# M850X.net
KiCad netlist of a schematic drawn in EAGLE
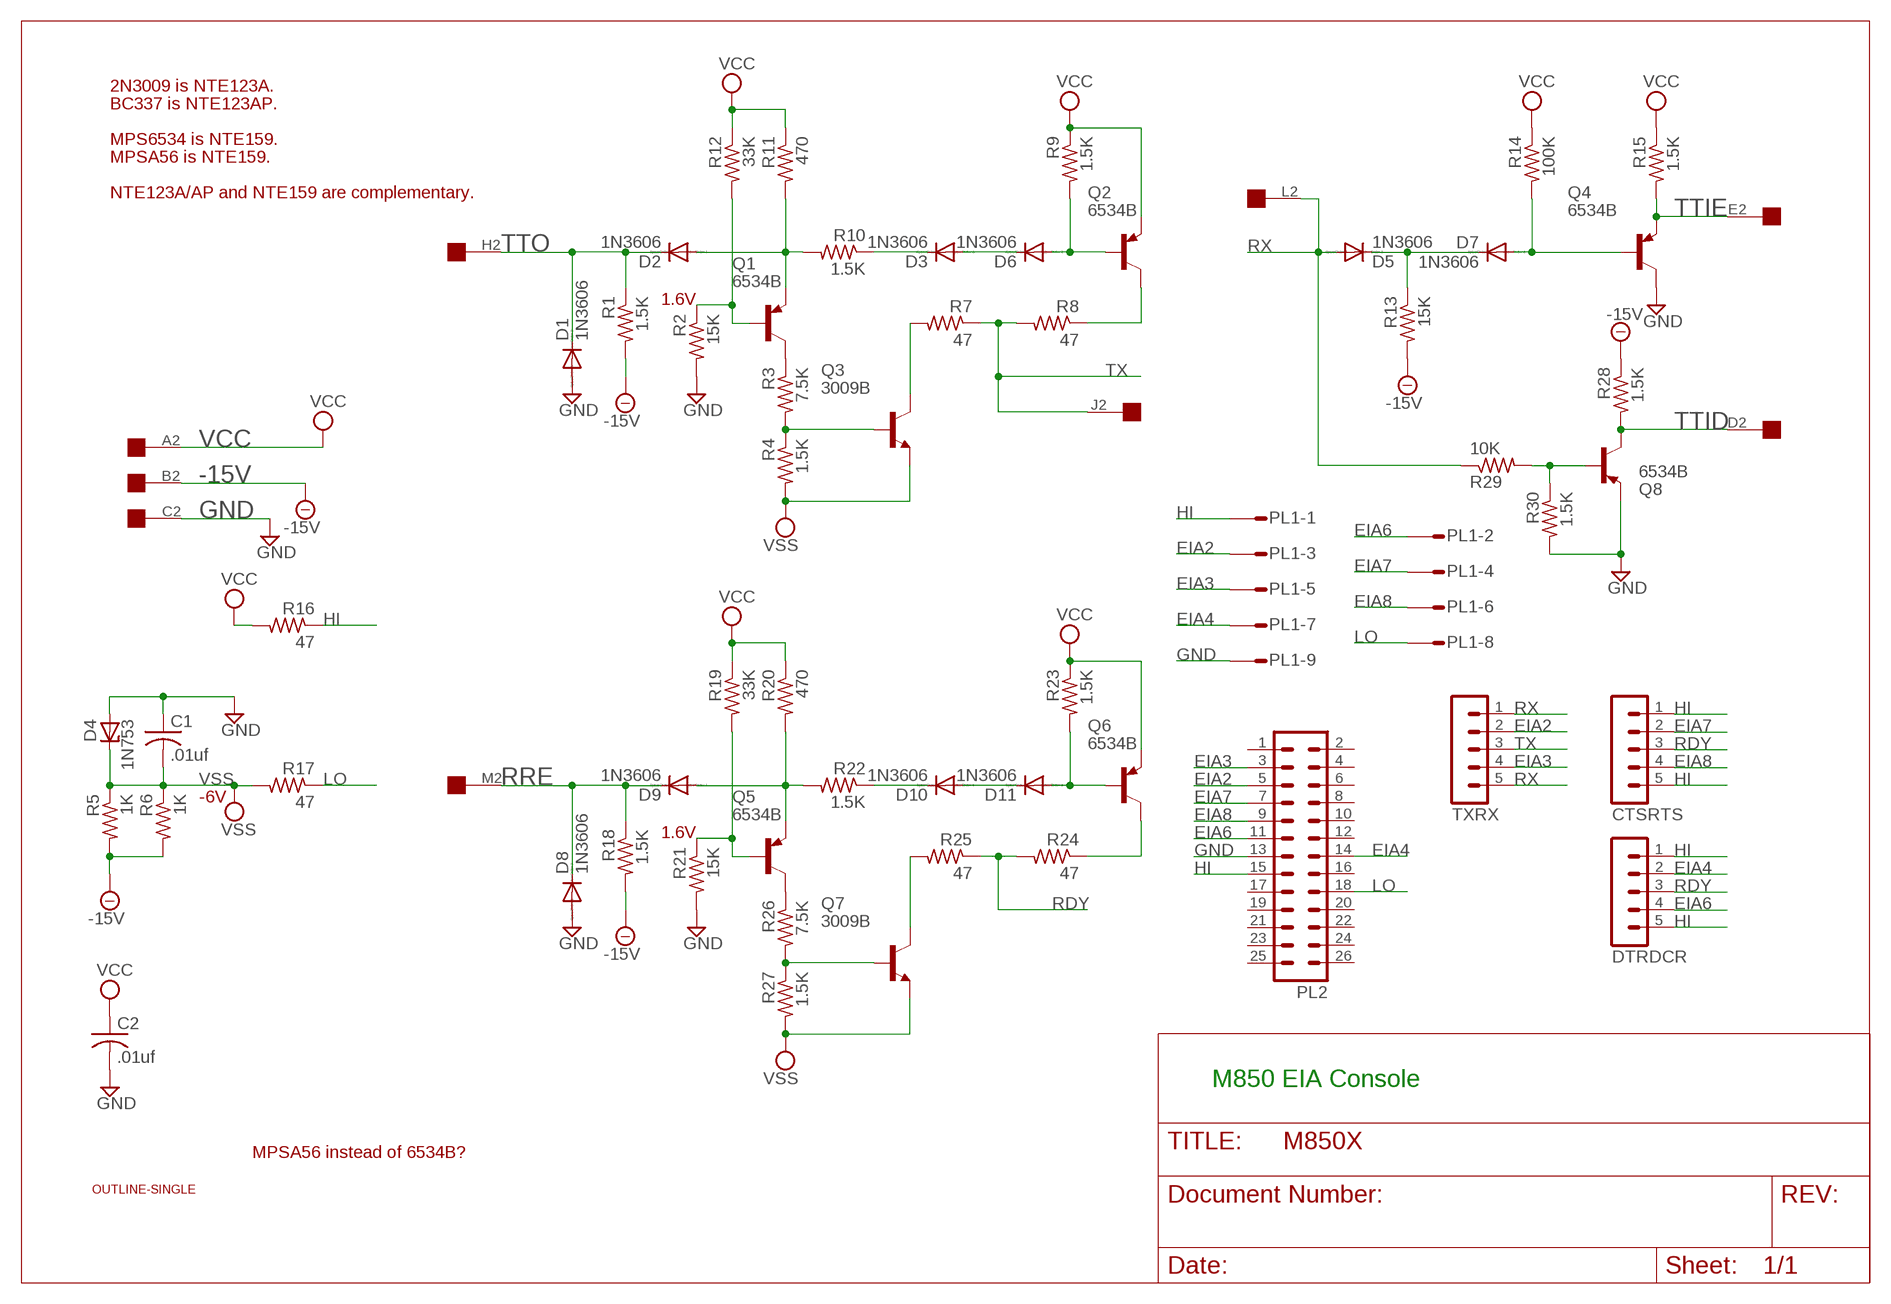
[diagram p0: schematic, sheet 1]

(export (version "E")
  (design (tool "Eeschema 10.0.6"))
  (components
    (comp (ref "C1")
      (value ".01uf")
      (footprint "eagle-import:C050-025X075")
      (libsource (lib "eagle-import") (part "C-US050-025X075"))
    )
    (comp (ref "C2")
      (value ".01uf")
      (footprint "eagle-import:C050-025X075")
      (libsource (lib "eagle-import") (part "C-US050-025X075"))
    )
    (comp (ref "CTSRTS")
      (value "MA05-1")
      (footprint "eagle-import:MA05-1")
      (libsource (lib "eagle-import") (part "MA05-1"))
    )
    (comp (ref "D1")
      (value "1N3606")
      (footprint "eagle-import:DO35-10")
      (libsource (lib "eagle-import") (part "1N4148DO35-10"))
    )
    (comp (ref "D2")
      (value "1N3606")
      (footprint "eagle-import:DO35-10")
      (libsource (lib "eagle-import") (part "1N4148DO35-10"))
    )
    (comp (ref "D3")
      (value "1N3606")
      (footprint "eagle-import:DO35-10")
      (libsource (lib "eagle-import") (part "1N4148DO35-10"))
    )
    (comp (ref "D4")
      (value "1N753")
      (footprint "eagle-import:DO35Z10")
      (libsource (lib "eagle-import") (part "ZENER-DIODEDO35Z10"))
    )
    (comp (ref "D5")
      (value "1N3606")
      (footprint "eagle-import:DO35-10")
      (libsource (lib "eagle-import") (part "1N4148DO35-10"))
    )
    (comp (ref "D6")
      (value "1N3606")
      (footprint "eagle-import:DO35-10")
      (libsource (lib "eagle-import") (part "1N4148DO35-10"))
    )
    (comp (ref "D7")
      (value "1N3606")
      (footprint "eagle-import:DO35-10")
      (libsource (lib "eagle-import") (part "1N4148DO35-10"))
    )
    (comp (ref "D8")
      (value "1N3606")
      (footprint "eagle-import:DO35-10")
      (libsource (lib "eagle-import") (part "1N4148DO35-10"))
    )
    (comp (ref "D9")
      (value "1N3606")
      (footprint "eagle-import:DO35-10")
      (libsource (lib "eagle-import") (part "1N4148DO35-10"))
    )
    (comp (ref "D10")
      (value "1N3606")
      (footprint "eagle-import:DO35-10")
      (libsource (lib "eagle-import") (part "1N4148DO35-10"))
    )
    (comp (ref "D11")
      (value "1N3606")
      (footprint "eagle-import:DO35-10")
      (libsource (lib "eagle-import") (part "1N4148DO35-10"))
    )
    (comp (ref "DTRDCR")
      (value "MA05-1")
      (footprint "eagle-import:MA05-1")
      (libsource (lib "eagle-import") (part "MA05-1"))
    )
    (comp (ref "EDGE")
      (value "EDGE-1")
      (footprint "eagle-import:EDGE-CON1")
      (libsource (lib "eagle-import") (part "EDGE-1"))
    )
    (comp (ref "PL1")
      (value "10HS")
      (footprint "eagle-import:10H")
      (libsource (lib "eagle-import") (part "10HS"))
    )
    (comp (ref "PL2")
      (value "26H")
      (footprint "eagle-import:26H")
      (libsource (lib "eagle-import") (part "26H"))
    )
    (comp (ref "Q1")
      (value "6534B")
      (footprint "eagle-import:TO92_")
      (libsource (lib "eagle-import") (part "-PNP-TO92/"))
    )
    (comp (ref "Q2")
      (value "6534B")
      (footprint "eagle-import:TO92_")
      (libsource (lib "eagle-import") (part "-PNP-TO92/"))
    )
    (comp (ref "Q3")
      (value "3009B")
      (footprint "eagle-import:TO18-")
      (libsource (lib "eagle-import") (part "-NPN-TO18-"))
    )
    (comp (ref "Q4")
      (value "6534B")
      (footprint "eagle-import:TO92_")
      (libsource (lib "eagle-import") (part "-PNP-TO92/"))
    )
    (comp (ref "Q5")
      (value "6534B")
      (footprint "eagle-import:TO92_")
      (libsource (lib "eagle-import") (part "-PNP-TO92/"))
    )
    (comp (ref "Q6")
      (value "6534B")
      (footprint "eagle-import:TO92_")
      (libsource (lib "eagle-import") (part "-PNP-TO92/"))
    )
    (comp (ref "Q7")
      (value "3009B")
      (footprint "eagle-import:TO18-")
      (libsource (lib "eagle-import") (part "-NPN-TO18-"))
    )
    (comp (ref "Q8")
      (value "6534B")
      (footprint "eagle-import:TO92_")
      (libsource (lib "eagle-import") (part "-PNP-TO92/"))
    )
    (comp (ref "R1")
      (value "1.5K")
      (footprint "eagle-import:0207_10")
      (libsource (lib "eagle-import") (part "R-US_0207/10"))
    )
    (comp (ref "R2")
      (value "15K")
      (footprint "eagle-import:0207_10")
      (libsource (lib "eagle-import") (part "R-US_0207/10"))
    )
    (comp (ref "R3")
      (value "7.5K")
      (footprint "eagle-import:0207_10")
      (libsource (lib "eagle-import") (part "R-US_0207/10"))
    )
    (comp (ref "R4")
      (value "1.5K")
      (footprint "eagle-import:0207_10")
      (libsource (lib "eagle-import") (part "R-US_0207/10"))
    )
    (comp (ref "R5")
      (value "1K")
      (footprint "eagle-import:0207_10")
      (libsource (lib "eagle-import") (part "R-US_0207/10"))
    )
    (comp (ref "R6")
      (value "1K")
      (footprint "eagle-import:0207_10")
      (libsource (lib "eagle-import") (part "R-US_0207/10"))
    )
    (comp (ref "R7")
      (value "47")
      (footprint "eagle-import:0207_10")
      (libsource (lib "eagle-import") (part "R-US_0207/10"))
    )
    (comp (ref "R8")
      (value "47")
      (footprint "eagle-import:0207_10")
      (libsource (lib "eagle-import") (part "R-US_0207/10"))
    )
    (comp (ref "R9")
      (value "1.5K")
      (footprint "eagle-import:0207_10")
      (libsource (lib "eagle-import") (part "R-US_0207/10"))
    )
    (comp (ref "R10")
      (value "1.5K")
      (footprint "eagle-import:0207_10")
      (libsource (lib "eagle-import") (part "R-US_0207/10"))
    )
    (comp (ref "R11")
      (value "470")
      (footprint "eagle-import:0207_10")
      (libsource (lib "eagle-import") (part "R-US_0207/10"))
    )
    (comp (ref "R12")
      (value "33K")
      (footprint "eagle-import:0207_10")
      (libsource (lib "eagle-import") (part "R-US_0207/10"))
    )
    (comp (ref "R13")
      (value "15K")
      (footprint "eagle-import:0207_10")
      (libsource (lib "eagle-import") (part "R-US_0207/10"))
    )
    (comp (ref "R14")
      (value "100K")
      (footprint "eagle-import:0207_10")
      (libsource (lib "eagle-import") (part "R-US_0207/10"))
    )
    (comp (ref "R15")
      (value "1.5K")
      (footprint "eagle-import:0207_10")
      (libsource (lib "eagle-import") (part "R-US_0207/10"))
    )
    (comp (ref "R16")
      (value "47")
      (footprint "eagle-import:0207_10")
      (libsource (lib "eagle-import") (part "R-US_0207/10"))
    )
    (comp (ref "R17")
      (value "47")
      (footprint "eagle-import:0207_10")
      (libsource (lib "eagle-import") (part "R-US_0207/10"))
    )
    (comp (ref "R18")
      (value "1.5K")
      (footprint "eagle-import:0207_10")
      (libsource (lib "eagle-import") (part "R-US_0207/10"))
    )
    (comp (ref "R19")
      (value "33K")
      (footprint "eagle-import:0207_10")
      (libsource (lib "eagle-import") (part "R-US_0207/10"))
    )
    (comp (ref "R20")
      (value "470")
      (footprint "eagle-import:0207_10")
      (libsource (lib "eagle-import") (part "R-US_0207/10"))
    )
    (comp (ref "R21")
      (value "15K")
      (footprint "eagle-import:0207_10")
      (libsource (lib "eagle-import") (part "R-US_0207/10"))
    )
    (comp (ref "R22")
      (value "1.5K")
      (footprint "eagle-import:0207_10")
      (libsource (lib "eagle-import") (part "R-US_0207/10"))
    )
    (comp (ref "R23")
      (value "1.5K")
      (footprint "eagle-import:0207_10")
      (libsource (lib "eagle-import") (part "R-US_0207/10"))
    )
    (comp (ref "R24")
      (value "47")
      (footprint "eagle-import:0207_10")
      (libsource (lib "eagle-import") (part "R-US_0207/10"))
    )
    (comp (ref "R25")
      (value "47")
      (footprint "eagle-import:0207_10")
      (libsource (lib "eagle-import") (part "R-US_0207/10"))
    )
    (comp (ref "R26")
      (value "7.5K")
      (footprint "eagle-import:0207_10")
      (libsource (lib "eagle-import") (part "R-US_0207/10"))
    )
    (comp (ref "R27")
      (value "1.5K")
      (footprint "eagle-import:0207_10")
      (libsource (lib "eagle-import") (part "R-US_0207/10"))
    )
    (comp (ref "R28")
      (value "1.5K")
      (footprint "eagle-import:0207_10")
      (libsource (lib "eagle-import") (part "R-US_0207/10"))
    )
    (comp (ref "R29")
      (value "10K")
      (footprint "eagle-import:0207_10")
      (libsource (lib "eagle-import") (part "R-US_0207/10"))
    )
    (comp (ref "R30")
      (value "1.5K")
      (footprint "eagle-import:0207_10")
      (libsource (lib "eagle-import") (part "R-US_0207/10"))
    )
    (comp (ref "TXRX")
      (value "MA05-1")
      (footprint "eagle-import:MA05-1")
      (libsource (lib "eagle-import") (part "MA05-1"))
    )
    (comp (ref "U$1")
      (value "OUTLINE-SINGLE")
      (footprint "eagle-import:SINGLE")
      (libsource (lib "eagle-import") (part "OUTLINE-SINGLE"))
    )
  )
  (nets
    (net (code "1") (name "-15V") (class "Default")
      (node (ref "EDGE") (pin "B2") (pinfunction "1_B2") (pintype "bidirectional"))
      (node (ref "R1") (pin "2") (pinfunction "2_2") (pintype "passive"))
      (node (ref "R13") (pin "2") (pinfunction "2_2") (pintype "passive"))
      (node (ref "R18") (pin "2") (pinfunction "2_2") (pintype "passive"))
      (node (ref "R28") (pin "1") (pinfunction "1_1") (pintype "passive"))
      (node (ref "R5") (pin "2") (pinfunction "2_2") (pintype "passive"))
      (node (ref "R6") (pin "2") (pinfunction "2_2") (pintype "passive"))
    )
    (net (code "2") (name "/EIA2") (class "Default")
      (node (ref "PL1") (pin "3") (pinfunction "S_3") (pintype "passive"))
      (node (ref "PL2") (pin "5") (pinfunction "5_5") (pintype "passive"))
      (node (ref "TXRX") (pin "2") (pinfunction "2_2") (pintype "passive"))
    )
    (net (code "3") (name "/EIA3") (class "Default")
      (node (ref "PL1") (pin "5") (pinfunction "S_5") (pintype "passive"))
      (node (ref "PL2") (pin "3") (pinfunction "3_3") (pintype "passive"))
      (node (ref "TXRX") (pin "4") (pinfunction "4_4") (pintype "passive"))
    )
    (net (code "4") (name "/EIA4") (class "Default")
      (node (ref "DTRDCR") (pin "2") (pinfunction "2_2") (pintype "passive"))
      (node (ref "PL1") (pin "7") (pinfunction "S_7") (pintype "passive"))
      (node (ref "PL2") (pin "14") (pinfunction "14_14") (pintype "passive"))
    )
    (net (code "5") (name "/EIA6") (class "Default")
      (node (ref "DTRDCR") (pin "4") (pinfunction "4_4") (pintype "passive"))
      (node (ref "PL1") (pin "2") (pinfunction "S_2") (pintype "passive"))
      (node (ref "PL2") (pin "11") (pinfunction "11_11") (pintype "passive"))
    )
    (net (code "6") (name "/EIA7") (class "Default")
      (node (ref "CTSRTS") (pin "2") (pinfunction "2_2") (pintype "passive"))
      (node (ref "PL1") (pin "4") (pinfunction "S_4") (pintype "passive"))
      (node (ref "PL2") (pin "7") (pinfunction "7_7") (pintype "passive"))
    )
    (net (code "7") (name "/EIA8") (class "Default")
      (node (ref "CTSRTS") (pin "4") (pinfunction "4_4") (pintype "passive"))
      (node (ref "PL1") (pin "6") (pinfunction "S_6") (pintype "passive"))
      (node (ref "PL2") (pin "9") (pinfunction "9_9") (pintype "passive"))
    )
    (net (code "8") (name "/HI") (class "Default")
      (node (ref "CTSRTS") (pin "1") (pinfunction "1_1") (pintype "passive"))
      (node (ref "CTSRTS") (pin "5") (pinfunction "5_5") (pintype "passive"))
      (node (ref "DTRDCR") (pin "1") (pinfunction "1_1") (pintype "passive"))
      (node (ref "DTRDCR") (pin "5") (pinfunction "5_5") (pintype "passive"))
      (node (ref "PL1") (pin "1") (pinfunction "S_1") (pintype "passive"))
      (node (ref "PL2") (pin "15") (pinfunction "15_15") (pintype "passive"))
      (node (ref "R16") (pin "1") (pinfunction "1_1") (pintype "passive"))
    )
    (net (code "9") (name "/LO") (class "Default")
      (node (ref "PL1") (pin "8") (pinfunction "S_8") (pintype "passive"))
      (node (ref "PL2") (pin "18") (pinfunction "18_18") (pintype "passive"))
      (node (ref "R17") (pin "1") (pinfunction "1_1") (pintype "passive"))
    )
    (net (code "10") (name "/RDY") (class "Default")
      (node (ref "CTSRTS") (pin "3") (pinfunction "3_3") (pintype "passive"))
      (node (ref "DTRDCR") (pin "3") (pinfunction "3_3") (pintype "passive"))
      (node (ref "R24") (pin "2") (pinfunction "2_2") (pintype "passive"))
      (node (ref "R25") (pin "1") (pinfunction "1_1") (pintype "passive"))
    )
    (net (code "11") (name "/RRE") (class "Default")
      (node (ref "D8") (pin "C") (pinfunction "C_C") (pintype "passive"))
      (node (ref "D9") (pin "C") (pinfunction "C_C") (pintype "passive"))
      (node (ref "EDGE") (pin "M2") (pinfunction "1_M2") (pintype "bidirectional"))
      (node (ref "R18") (pin "1") (pinfunction "1_1") (pintype "passive"))
    )
    (net (code "12") (name "/RX") (class "Default")
      (node (ref "D5") (pin "A") (pinfunction "A_A") (pintype "passive"))
      (node (ref "EDGE") (pin "L2") (pinfunction "1_L2") (pintype "bidirectional"))
      (node (ref "R29") (pin "1") (pinfunction "1_1") (pintype "passive"))
      (node (ref "TXRX") (pin "1") (pinfunction "1_1") (pintype "passive"))
      (node (ref "TXRX") (pin "5") (pinfunction "5_5") (pintype "passive"))
    )
    (net (code "13") (name "/TTID") (class "Default")
      (node (ref "EDGE") (pin "D2") (pinfunction "1_D2") (pintype "bidirectional"))
      (node (ref "Q8") (pin "3") (pinfunction "C_3") (pintype "passive"))
      (node (ref "R28") (pin "2") (pinfunction "2_2") (pintype "passive"))
    )
    (net (code "14") (name "/TTIE") (class "Default")
      (node (ref "EDGE") (pin "E2") (pinfunction "1_E2") (pintype "bidirectional"))
      (node (ref "Q4") (pin "1") (pinfunction "E_1") (pintype "passive"))
      (node (ref "R15") (pin "2") (pinfunction "2_2") (pintype "passive"))
    )
    (net (code "15") (name "/TTO") (class "Default")
      (node (ref "D1") (pin "C") (pinfunction "C_C") (pintype "passive"))
      (node (ref "D2") (pin "C") (pinfunction "C_C") (pintype "passive"))
      (node (ref "EDGE") (pin "H2") (pinfunction "1_H2") (pintype "bidirectional"))
      (node (ref "R1") (pin "1") (pinfunction "1_1") (pintype "passive"))
    )
    (net (code "16") (name "/TX") (class "Default")
      (node (ref "EDGE") (pin "J2") (pinfunction "1_J2") (pintype "bidirectional"))
      (node (ref "R7") (pin "1") (pinfunction "1_1") (pintype "passive"))
      (node (ref "R8") (pin "2") (pinfunction "2_2") (pintype "passive"))
      (node (ref "TXRX") (pin "3") (pinfunction "3_3") (pintype "passive"))
    )
    (net (code "17") (name "GND") (class "Default")
      (node (ref "C1") (pin "1") (pinfunction "1_1") (pintype "passive"))
      (node (ref "C2") (pin "2") (pinfunction "2_2") (pintype "passive"))
      (node (ref "D1") (pin "A") (pinfunction "A_A") (pintype "passive"))
      (node (ref "D4") (pin "A") (pinfunction "A_A") (pintype "passive"))
      (node (ref "D8") (pin "A") (pinfunction "A_A") (pintype "passive"))
      (node (ref "EDGE") (pin "C2") (pinfunction "1_C2") (pintype "bidirectional"))
      (node (ref "PL1") (pin "9") (pinfunction "S_9") (pintype "passive"))
      (node (ref "PL2") (pin "13") (pinfunction "13_13") (pintype "passive"))
      (node (ref "Q4") (pin "3") (pinfunction "C_3") (pintype "passive"))
      (node (ref "Q8") (pin "1") (pinfunction "E_1") (pintype "passive"))
      (node (ref "R2") (pin "2") (pinfunction "2_2") (pintype "passive"))
      (node (ref "R21") (pin "2") (pinfunction "2_2") (pintype "passive"))
      (node (ref "R30") (pin "2") (pinfunction "2_2") (pintype "passive"))
    )
    (net (code "18") (name "Net-(D3-PadA)") (class "Default")
      (node (ref "D3") (pin "A") (pinfunction "A_A") (pintype "passive"))
      (node (ref "D6") (pin "C") (pinfunction "C_C") (pintype "passive"))
    )
    (net (code "19") (name "Net-(D3-PadC)") (class "Default")
      (node (ref "D3") (pin "C") (pinfunction "C_C") (pintype "passive"))
      (node (ref "R10") (pin "1") (pinfunction "1_1") (pintype "passive"))
    )
    (net (code "20") (name "Net-(D5-PadC)") (class "Default")
      (node (ref "D5") (pin "C") (pinfunction "C_C") (pintype "passive"))
      (node (ref "D7") (pin "C") (pinfunction "C_C") (pintype "passive"))
      (node (ref "R13") (pin "1") (pinfunction "1_1") (pintype "passive"))
    )
    (net (code "21") (name "Net-(D10-PadA)") (class "Default")
      (node (ref "D10") (pin "A") (pinfunction "A_A") (pintype "passive"))
      (node (ref "D11") (pin "C") (pinfunction "C_C") (pintype "passive"))
    )
    (net (code "22") (name "Net-(D10-PadC)") (class "Default")
      (node (ref "D10") (pin "C") (pinfunction "C_C") (pintype "passive"))
      (node (ref "R22") (pin "1") (pinfunction "1_1") (pintype "passive"))
    )
    (net (code "23") (name "Net-(Q1-B)") (class "Default")
      (node (ref "Q1") (pin "2") (pinfunction "B_2") (pintype "passive"))
      (node (ref "R12") (pin "2") (pinfunction "2_2") (pintype "passive"))
      (node (ref "R2") (pin "1") (pinfunction "1_1") (pintype "passive"))
    )
    (net (code "24") (name "Net-(Q1-C)") (class "Default")
      (node (ref "Q1") (pin "3") (pinfunction "C_3") (pintype "passive"))
      (node (ref "R3") (pin "1") (pinfunction "1_1") (pintype "passive"))
    )
    (net (code "25") (name "Net-(Q1-E)") (class "Default")
      (node (ref "D2") (pin "A") (pinfunction "A_A") (pintype "passive"))
      (node (ref "Q1") (pin "1") (pinfunction "E_1") (pintype "passive"))
      (node (ref "R10") (pin "2") (pinfunction "2_2") (pintype "passive"))
      (node (ref "R11") (pin "2") (pinfunction "2_2") (pintype "passive"))
    )
    (net (code "26") (name "Net-(Q2-B)") (class "Default")
      (node (ref "D6") (pin "A") (pinfunction "A_A") (pintype "passive"))
      (node (ref "Q2") (pin "2") (pinfunction "B_2") (pintype "passive"))
      (node (ref "R9") (pin "2") (pinfunction "2_2") (pintype "passive"))
    )
    (net (code "27") (name "Net-(Q2-C)") (class "Default")
      (node (ref "Q2") (pin "3") (pinfunction "C_3") (pintype "passive"))
      (node (ref "R8") (pin "1") (pinfunction "1_1") (pintype "passive"))
    )
    (net (code "28") (name "Net-(Q3-B)") (class "Default")
      (node (ref "Q3") (pin "2") (pinfunction "B_2") (pintype "passive"))
      (node (ref "R3") (pin "2") (pinfunction "2_2") (pintype "passive"))
      (node (ref "R4") (pin "1") (pinfunction "1_1") (pintype "passive"))
    )
    (net (code "29") (name "Net-(Q3-C)") (class "Default")
      (node (ref "Q3") (pin "3") (pinfunction "C_3") (pintype "passive"))
      (node (ref "R7") (pin "2") (pinfunction "2_2") (pintype "passive"))
    )
    (net (code "30") (name "Net-(Q4-B)") (class "Default")
      (node (ref "D7") (pin "A") (pinfunction "A_A") (pintype "passive"))
      (node (ref "Q4") (pin "2") (pinfunction "B_2") (pintype "passive"))
      (node (ref "R14") (pin "2") (pinfunction "2_2") (pintype "passive"))
    )
    (net (code "31") (name "Net-(Q5-B)") (class "Default")
      (node (ref "Q5") (pin "2") (pinfunction "B_2") (pintype "passive"))
      (node (ref "R19") (pin "2") (pinfunction "2_2") (pintype "passive"))
      (node (ref "R21") (pin "1") (pinfunction "1_1") (pintype "passive"))
    )
    (net (code "32") (name "Net-(Q5-C)") (class "Default")
      (node (ref "Q5") (pin "3") (pinfunction "C_3") (pintype "passive"))
      (node (ref "R26") (pin "1") (pinfunction "1_1") (pintype "passive"))
    )
    (net (code "33") (name "Net-(Q5-E)") (class "Default")
      (node (ref "D9") (pin "A") (pinfunction "A_A") (pintype "passive"))
      (node (ref "Q5") (pin "1") (pinfunction "E_1") (pintype "passive"))
      (node (ref "R20") (pin "2") (pinfunction "2_2") (pintype "passive"))
      (node (ref "R22") (pin "2") (pinfunction "2_2") (pintype "passive"))
    )
    (net (code "34") (name "Net-(Q6-B)") (class "Default")
      (node (ref "D11") (pin "A") (pinfunction "A_A") (pintype "passive"))
      (node (ref "Q6") (pin "2") (pinfunction "B_2") (pintype "passive"))
      (node (ref "R23") (pin "2") (pinfunction "2_2") (pintype "passive"))
    )
    (net (code "35") (name "Net-(Q6-C)") (class "Default")
      (node (ref "Q6") (pin "3") (pinfunction "C_3") (pintype "passive"))
      (node (ref "R24") (pin "1") (pinfunction "1_1") (pintype "passive"))
    )
    (net (code "36") (name "Net-(Q7-B)") (class "Default")
      (node (ref "Q7") (pin "2") (pinfunction "B_2") (pintype "passive"))
      (node (ref "R26") (pin "2") (pinfunction "2_2") (pintype "passive"))
      (node (ref "R27") (pin "1") (pinfunction "1_1") (pintype "passive"))
    )
    (net (code "37") (name "Net-(Q7-C)") (class "Default")
      (node (ref "Q7") (pin "3") (pinfunction "C_3") (pintype "passive"))
      (node (ref "R25") (pin "2") (pinfunction "2_2") (pintype "passive"))
    )
    (net (code "38") (name "Net-(Q8-B)") (class "Default")
      (node (ref "Q8") (pin "2") (pinfunction "B_2") (pintype "passive"))
      (node (ref "R29") (pin "2") (pinfunction "2_2") (pintype "passive"))
      (node (ref "R30") (pin "1") (pinfunction "1_1") (pintype "passive"))
    )
    (net (code "39") (name "VCC") (class "Default")
      (node (ref "C2") (pin "1") (pinfunction "1_1") (pintype "passive"))
      (node (ref "EDGE") (pin "A2") (pinfunction "1_A2") (pintype "bidirectional"))
      (node (ref "Q2") (pin "1") (pinfunction "E_1") (pintype "passive"))
      (node (ref "Q6") (pin "1") (pinfunction "E_1") (pintype "passive"))
      (node (ref "R11") (pin "1") (pinfunction "1_1") (pintype "passive"))
      (node (ref "R12") (pin "1") (pinfunction "1_1") (pintype "passive"))
      (node (ref "R14") (pin "1") (pinfunction "1_1") (pintype "passive"))
      (node (ref "R15") (pin "1") (pinfunction "1_1") (pintype "passive"))
      (node (ref "R16") (pin "2") (pinfunction "2_2") (pintype "passive"))
      (node (ref "R19") (pin "1") (pinfunction "1_1") (pintype "passive"))
      (node (ref "R20") (pin "1") (pinfunction "1_1") (pintype "passive"))
      (node (ref "R23") (pin "1") (pinfunction "1_1") (pintype "passive"))
      (node (ref "R9") (pin "1") (pinfunction "1_1") (pintype "passive"))
    )
    (net (code "40") (name "VSS") (class "Default")
      (node (ref "C1") (pin "2") (pinfunction "2_2") (pintype "passive"))
      (node (ref "D4") (pin "C") (pinfunction "C_C") (pintype "passive"))
      (node (ref "Q3") (pin "1") (pinfunction "E_1") (pintype "passive"))
      (node (ref "Q7") (pin "1") (pinfunction "E_1") (pintype "passive"))
      (node (ref "R17") (pin "2") (pinfunction "2_2") (pintype "passive"))
      (node (ref "R27") (pin "2") (pinfunction "2_2") (pintype "passive"))
      (node (ref "R4") (pin "2") (pinfunction "2_2") (pintype "passive"))
      (node (ref "R5") (pin "1") (pinfunction "1_1") (pintype "passive"))
      (node (ref "R6") (pin "1") (pinfunction "1_1") (pintype "passive"))
    )
    (net (code "41") (name "unconnected-(PL2-Pad1)") (class "Default")
      (node (ref "PL2") (pin "1") (pinfunction "1_1") (pintype "passive"))
    )
    (net (code "42") (name "unconnected-(PL2-Pad2)") (class "Default")
      (node (ref "PL2") (pin "2") (pinfunction "2_2") (pintype "passive"))
    )
    (net (code "43") (name "unconnected-(PL2-Pad4)") (class "Default")
      (node (ref "PL2") (pin "4") (pinfunction "4_4") (pintype "passive"))
    )
    (net (code "44") (name "unconnected-(PL2-Pad6)") (class "Default")
      (node (ref "PL2") (pin "6") (pinfunction "6_6") (pintype "passive"))
    )
    (net (code "45") (name "unconnected-(PL2-Pad8)") (class "Default")
      (node (ref "PL2") (pin "8") (pinfunction "8_8") (pintype "passive"))
    )
    (net (code "46") (name "unconnected-(PL2-Pad10)") (class "Default")
      (node (ref "PL2") (pin "10") (pinfunction "10_10") (pintype "passive"))
    )
    (net (code "47") (name "unconnected-(PL2-Pad12)") (class "Default")
      (node (ref "PL2") (pin "12") (pinfunction "12_12") (pintype "passive"))
    )
    (net (code "48") (name "unconnected-(PL2-Pad16)") (class "Default")
      (node (ref "PL2") (pin "16") (pinfunction "16_16") (pintype "passive"))
    )
    (net (code "49") (name "unconnected-(PL2-Pad17)") (class "Default")
      (node (ref "PL2") (pin "17") (pinfunction "17_17") (pintype "passive"))
    )
    (net (code "50") (name "unconnected-(PL2-Pad19)") (class "Default")
      (node (ref "PL2") (pin "19") (pinfunction "19_19") (pintype "passive"))
    )
    (net (code "51") (name "unconnected-(PL2-Pad20)") (class "Default")
      (node (ref "PL2") (pin "20") (pinfunction "20_20") (pintype "passive"))
    )
    (net (code "52") (name "unconnected-(PL2-Pad21)") (class "Default")
      (node (ref "PL2") (pin "21") (pinfunction "21_21") (pintype "passive"))
    )
    (net (code "53") (name "unconnected-(PL2-Pad22)") (class "Default")
      (node (ref "PL2") (pin "22") (pinfunction "22_22") (pintype "passive"))
    )
    (net (code "54") (name "unconnected-(PL2-Pad23)") (class "Default")
      (node (ref "PL2") (pin "23") (pinfunction "23_23") (pintype "passive"))
    )
    (net (code "55") (name "unconnected-(PL2-Pad24)") (class "Default")
      (node (ref "PL2") (pin "24") (pinfunction "24_24") (pintype "passive"))
    )
    (net (code "56") (name "unconnected-(PL2-Pad25)") (class "Default")
      (node (ref "PL2") (pin "25") (pinfunction "25_25") (pintype "passive"))
    )
    (net (code "57") (name "unconnected-(PL2-Pad26)") (class "Default")
      (node (ref "PL2") (pin "26") (pinfunction "26_26") (pintype "passive"))
    )
  )
)
